# P09_USER_LED_FAN_WD_RTC.net
KiCad netlist of a schematic drawn in Altium Designer
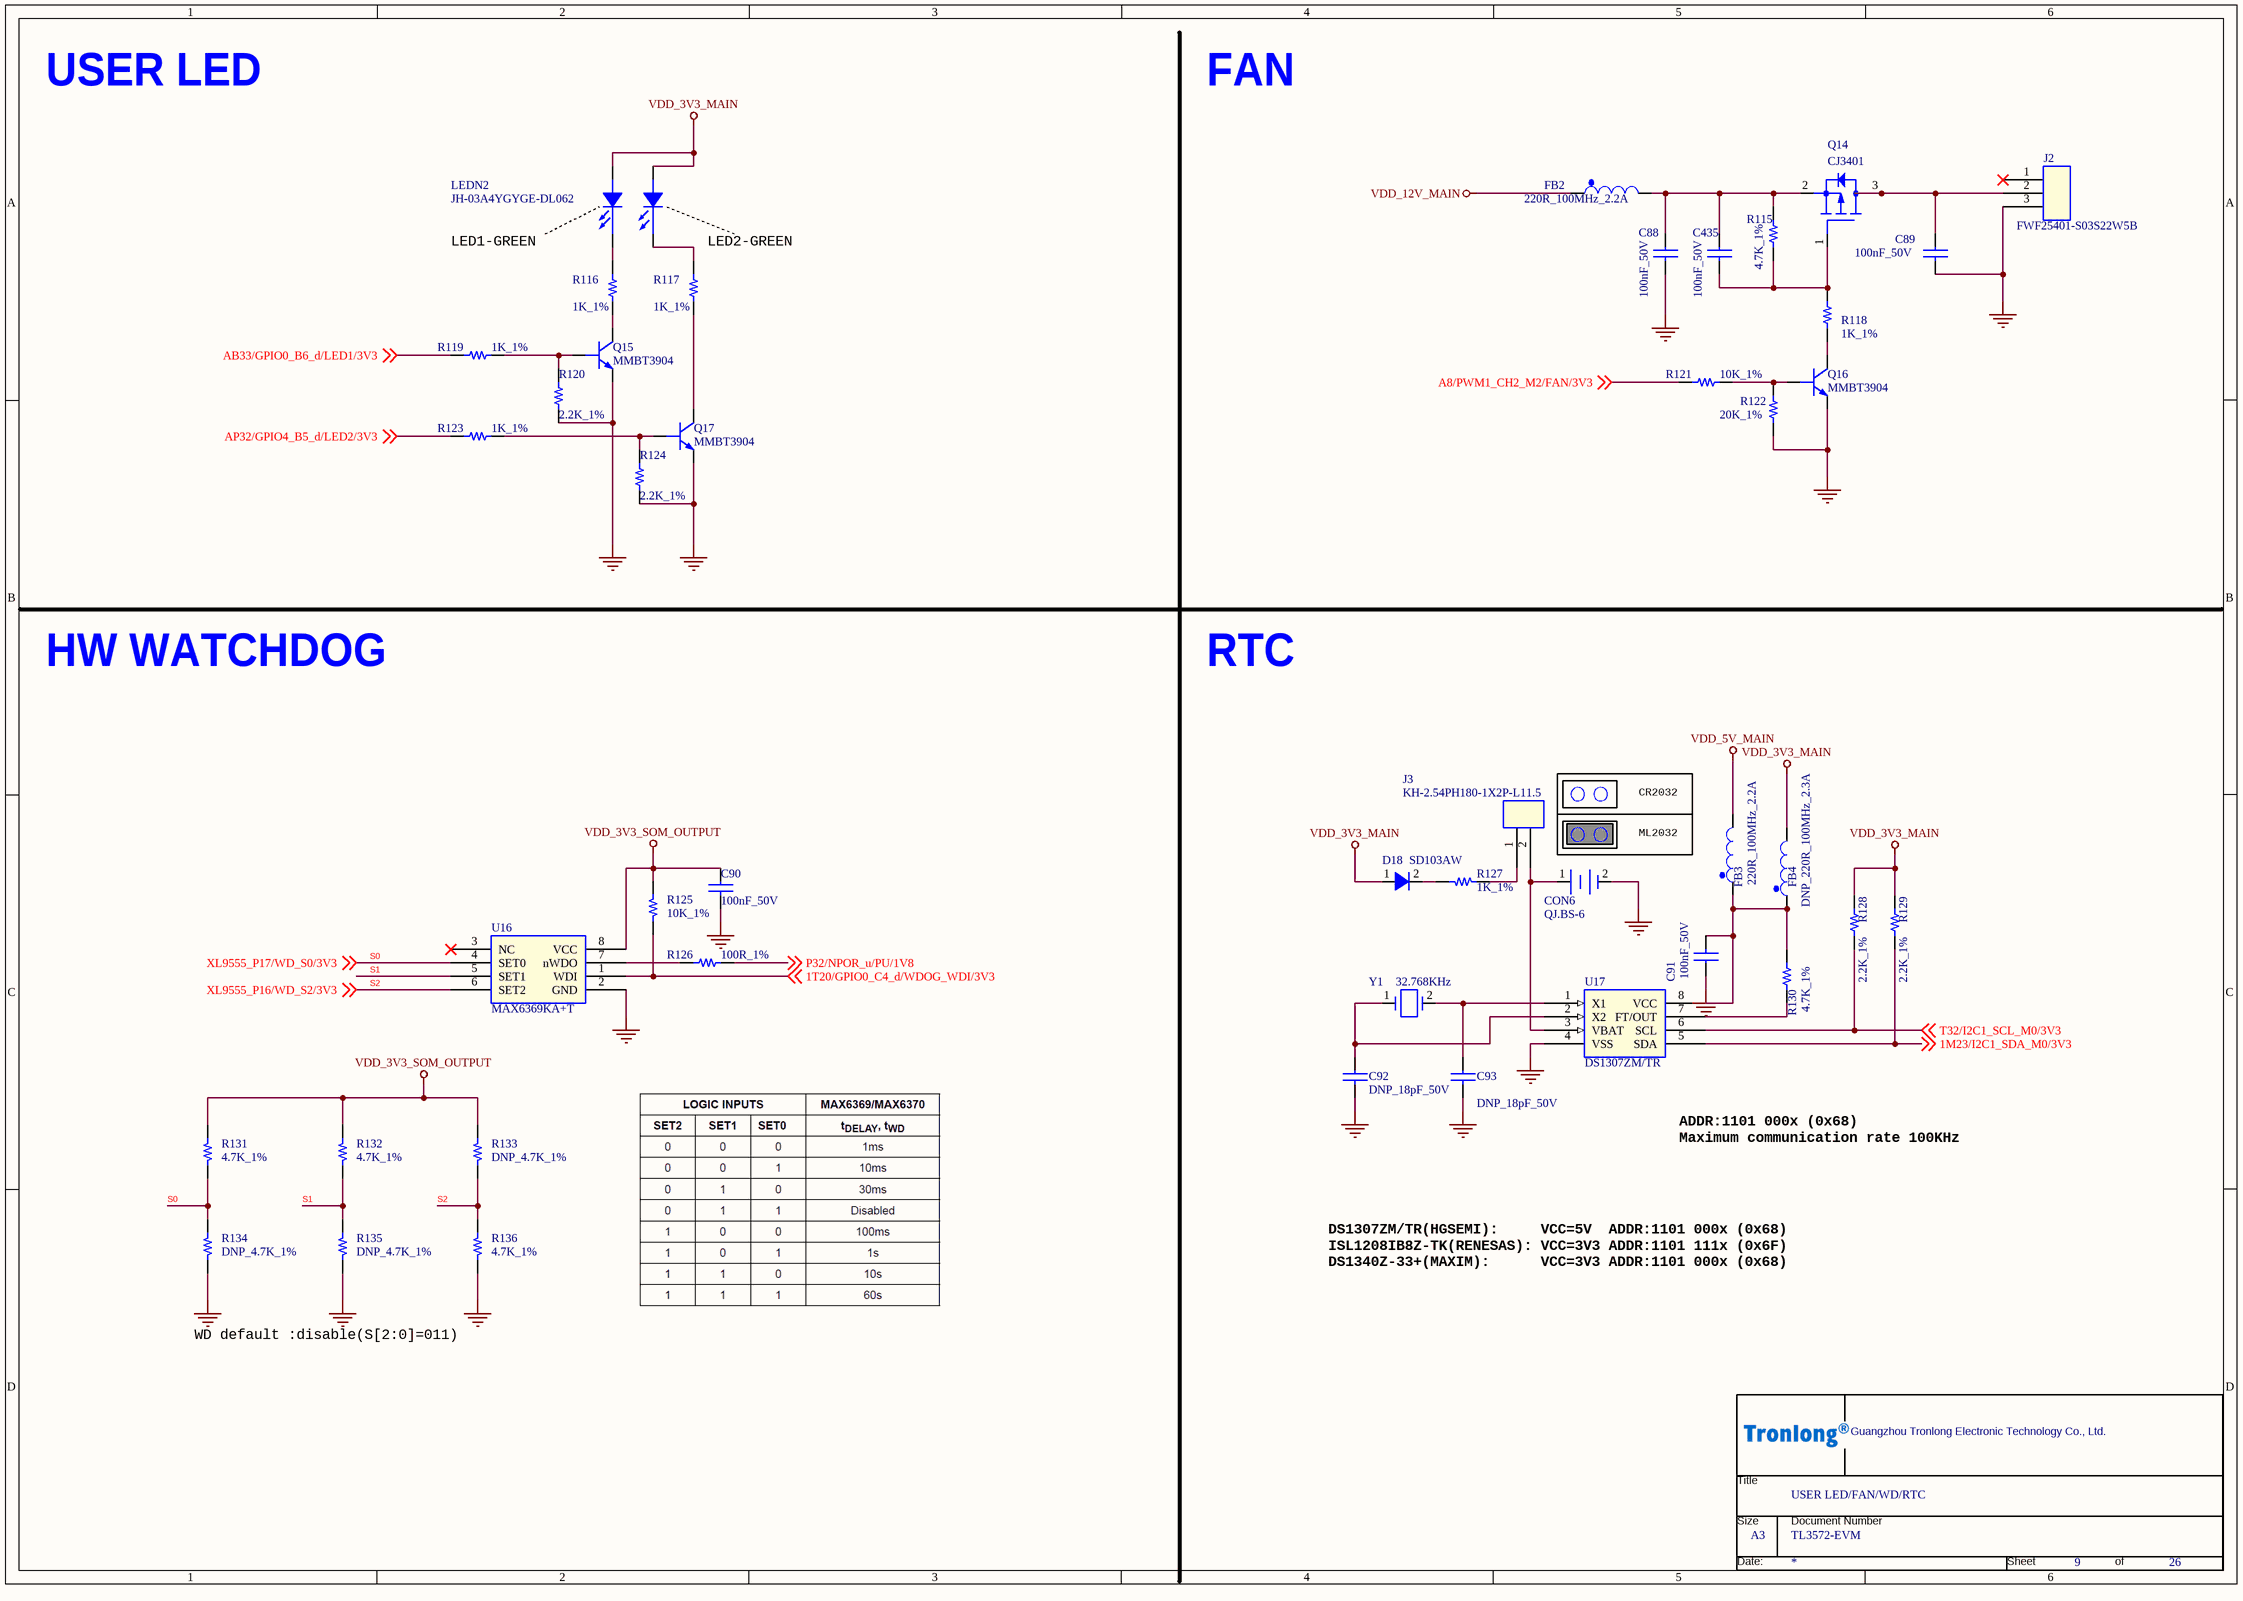
[diagram p0: P09_USER LED_FAN_WD_RTC.SchDoc]

(export (version "E")
  (design (tool "Eeschema 10.0.6"))
  (components
    (comp (ref "*")
      (value "TL_NEW")
      (fields
        (field (name "PAGE COUNT") "26")
        (field (name "PAGE NUMBER") "9")
        (field (name "PAGE SIZE") "A3")
        (field (name "ORGNAME") "Guangzhou Tronlong Electronic Technology Co., Ltd.")
        (field (name "TITLE") "USER LED/FAN/WD/RTC")
        (field (name "DOC") "TL3572-EVM")
      )
      (libsource (lib "*") (part "TL_NEW"))
    )
    (comp (ref "C88")
      (value "100nF_50V")
      (footprint "C0402")
      (description "贴片陶瓷电容,100nF,10%,50V,X7R")
      (fields
        (field (name "MANUFACTURER PARTNUMBER") "0402B104K500NT")
        (field (name "MANUFACTURER") "广东风华高新科技股份有限公司（FH）")
      )
      (libsource (lib "*") (part "CAP NP_Dup2"))
    )
    (comp (ref "C89")
      (value "100nF_50V")
      (footprint "C0402")
      (description "贴片陶瓷电容,100nF,10%,50V,X7R")
      (fields
        (field (name "MANUFACTURER PARTNUMBER") "0402B104K500NT")
        (field (name "MANUFACTURER") "广东风华高新科技股份有限公司（FH）")
      )
      (libsource (lib "*") (part "CAP NP_Dup2"))
    )
    (comp (ref "C90")
      (value "100nF_50V")
      (footprint "C0402")
      (description "贴片陶瓷电容,100nF,10%,50V,X7R")
      (fields
        (field (name "MANUFACTURER PARTNUMBER") "0402B104K500NT")
        (field (name "MANUFACTURER") "广东风华高新科技股份有限公司（FH）")
      )
      (libsource (lib "*") (part "CAP NP_Dup2"))
    )
    (comp (ref "C91")
      (value "100nF_50V")
      (footprint "C0402")
      (description "贴片陶瓷电容,100nF,10%,50V,X7R")
      (fields
        (field (name "MANUFACTURER PARTNUMBER") "0402B104K500NT")
        (field (name "MANUFACTURER") "广东风华高新科技股份有限公司（FH）")
      )
      (libsource (lib "*") (part "CAP NP_Dup2"))
    )
    (comp (ref "C92")
      (value "DNP_18pF_50V")
      (footprint "C0603")
      (description "贴片陶瓷电容,18pF,5%,50V,COG")
      (fields
        (field (name "MANUFACTURER PARTNUMBER") "0603CG180J500NT")
        (field (name "MANUFACTURER") "广东风华高新科技股份有限公司（FH）")
      )
      (libsource (lib "*") (part "CAP NP_Dup2"))
    )
    (comp (ref "C93")
      (value "DNP_18pF_50V")
      (footprint "C0603")
      (description "贴片陶瓷电容,18pF,5%,50V,COG")
      (fields
        (field (name "MANUFACTURER PARTNUMBER") "0603CG180J500NT")
        (field (name "MANUFACTURER") "广东风华高新科技股份有限公司（FH）")
      )
      (libsource (lib "*") (part "CAP NP_Dup2"))
    )
    (comp (ref "C435")
      (value "100nF_50V")
      (footprint "C0402")
      (description "贴片陶瓷电容,100nF,10%,50V,X7R")
      (fields
        (field (name "MANUFACTURER PARTNUMBER") "0402B104K500NT")
        (field (name "MANUFACTURER") "广东风华高新科技股份有限公司（FH）")
      )
      (libsource (lib "*") (part "CAP NP_Dup2"))
    )
    (comp (ref "CON6")
      (value "QJ.BS-6")
      (footprint "CON_BATTERY_CR2032")
      (description "贴片纽扣电池座,CR2032,2P,180度")
      (fields (field (name "MANUFACTURER") "深圳市琦捷电子有限公司（QIJEY）"))
      (libsource (lib "*") (part "BATTERY"))
    )
    (comp (ref "D18")
      (value "SD103AW")
      (footprint "SOD-123_NEW")
      (description "肖特基二极管,VR=40V,IF=350mA,VF=0.37V@20mA,trr=10ns")
      (fields (field (name "TIINTPARTNUMBER") "1E0013") (field (name "MFR") "On Semiconductor"))
      (libsource (lib "*") (part "Diode200mA250V_1"))
    )
    (comp (ref "FB2")
      (value "220R_100MHz_2.2A")
      (footprint "L0603")
      (description "磁珠,50mΩ,2.2A,220R@100MHz")
      (fields
        (field (name "MANUFACTURER PARTNUMBER") "UPZ1608U221-2R2TF")
        (field (name "MANUFACTURER") "深圳顺络电子股份有限公司（Sunlord）")
      )
      (libsource (lib "*") (part "FB_0"))
    )
    (comp (ref "FB3")
      (value "220R_100MHz_2.2A")
      (footprint "L0603")
      (description "磁珠,50mΩ,2.2A,220R@100MHz")
      (fields
        (field (name "MANUFACTURER PARTNUMBER") "UPZ1608U221-2R2TF")
        (field (name "MANUFACTURER") "深圳顺络电子股份有限公司（Sunlord）")
      )
      (libsource (lib "*") (part "FERRITE BEAD_Dup1"))
    )
    (comp (ref "FB4")
      (value "DNP_220R_100MHz_2.3A")
      (footprint "L0603")
      (description "磁珠,50mΩ,2.3A,220R@100MHz")
      (fields
        (field (name "MANUFACTURER") "深圳顺络电子股份有限公司（Sunlord）")
        (field (name "MANUFACTURER PARTNUMBER") "UPZ1608U221-2R3TF")
      )
      (libsource (lib "*") (part "FERRITE BEAD_Dup1"))
    )
    (comp (ref "J2")
      (value "FWF25401-S03S22W5B")
      (footprint "mol22-23-2031")
      (description "插件针座连接器,3P,间距2.54mm,180度,白色")
      (fields (field (name "MANUFACTURER") "深圳特思嘉工业电子有限公司（TXGA）"))
      (libsource (lib "*") (part "CON3"))
    )
    (comp (ref "J3")
      (value "KH-2.54PH180-1X2P-L11.5")
      (footprint "header_1x2p_2d54_male")
      (description "插件单排排针,1x2P,2.54mm,180度")
      (fields (field (name "MANUFACTURER") "深圳市金航标电子有限公司(kinghelm)"))
      (libsource (lib "*") (part "CON2_0"))
    )
    (comp (ref "LEDN2")
      (value "JH-03A4YGYGE-DL062")
      (footprint "led-th_4p-l12d8-w4d6")
      (description "直插式发光二极管,绿色,带灯座")
      (fields
        (field (name "MANUFACTURER") "深圳市巨弘光电有限公司（JUHLIGHT）")
        (field (name "MANUFACTURER PARTNUMBER") "JH-03B2YG1E-DL")
      )
      (libsource (lib "*") (part "LED_4"))
    )
    (comp (ref "Q14")
      (value "CJ3401")
      (footprint "SOT23-3")
      (description "MOSFET,P沟道,VDSS=-30V,VGSS=±12V,ID=-4.2A,PD=0.35W,VGS(th)=-1.3V")
      (fields (field (name "MANUFACTURER") "江苏长晶科技股份有限公司（JSCJ）"))
      (libsource (lib "*") (part "MOSFET P SOT_Dup1"))
    )
    (comp (ref "Q15")
      (value "MMBT3904")
      (footprint "SOT23-3_DBZ3")
      (description "BJT,NPN,Vceo=40V,Ic=200mA,fT=300MHz,PD=200mW")
      (fields (field (name "MANUFACTURER") "江苏长晶科技股份有限公司（JSCJ）"))
      (libsource (lib "*") (part "MMBT3904/SOT"))
    )
    (comp (ref "Q16")
      (value "MMBT3904")
      (footprint "SOT23-3_DBZ3")
      (description "BJT,NPN,Vceo=40V,Ic=200mA,fT=300MHz,PD=200mW")
      (fields (field (name "MANUFACTURER") "江苏长晶科技股份有限公司（JSCJ）"))
      (libsource (lib "*") (part "MMBT3904/SOT"))
    )
    (comp (ref "Q17")
      (value "MMBT3904")
      (footprint "SOT23-3_DBZ3")
      (description "BJT,NPN,Vceo=40V,Ic=200mA,fT=300MHz,PD=200mW")
      (fields (field (name "MANUFACTURER") "江苏长晶科技股份有限公司（JSCJ）"))
      (libsource (lib "*") (part "MMBT3904/SOT"))
    )
    (comp (ref "R115")
      (value "4.7K_1%")
      (footprint "R0402")
      (description "贴片电阻,4.7K,±1%,1/16W")
      (fields
        (field (name "MANUFACTURER") "广东风华高新科技股份有限公司（FH）")
        (field (name "MISTRAL PART NO") "110009031036-R")
      )
      (libsource (lib "*") (part "Resistor_Dup3"))
    )
    (comp (ref "R116")
      (value "1K_1%")
      (footprint "R0603")
      (description "贴片电阻,1K,±1%,1/10W")
      (fields
        (field (name "MANUFACTURER PARTNUMBER") "RS-03K1001FT")
        (field (name "MANUFACTURER") "广东风华高新科技股份有限公司（FH）")
      )
      (libsource (lib "*") (part "Resistor_Dup4"))
    )
    (comp (ref "R117")
      (value "1K_1%")
      (footprint "R0603")
      (description "贴片电阻,1K,±1%,1/10W")
      (fields
        (field (name "MANUFACTURER") "广东风华高新科技股份有限公司（FH）")
        (field (name "MANUFACTURER PARTNUMBER") "RS-03K1001FT")
      )
      (libsource (lib "*") (part "Resistor_Dup4"))
    )
    (comp (ref "R118")
      (value "1K_1%")
      (footprint "R0603")
      (description "贴片电阻,1K,±1%,1/10W")
      (fields
        (field (name "MANUFACTURER") "广东风华高新科技股份有限公司（FH）")
        (field (name "MISTRAL PART NO") "110009031036-R")
      )
      (libsource (lib "*") (part "Resistor_Dup3"))
    )
    (comp (ref "R119")
      (value "1K_1%")
      (footprint "R0402")
      (description "贴片电阻,1K,±1%,1/16W")
      (fields
        (field (name "MANUFACTURER PARTNUMBER") "RC-02K1001FT")
        (field (name "MANUFACTURER") "广东风华高新科技股份有限公司（FH）")
      )
      (libsource (lib "*") (part "Resistor_Dup4"))
    )
    (comp (ref "R120")
      (value "2.2K_1%")
      (footprint "R0603")
      (description "贴片电阻,2.2K,±1%,1/10W")
      (fields
        (field (name "MANUFACTURER") "广东风华高新科技股份有限公司（FH）")
        (field (name "MANUFACTURER PARTNUMBER") "RS-03K2201FT")
      )
      (libsource (lib "*") (part "Resistor_Dup4"))
    )
    (comp (ref "R121")
      (value "10K_1%")
      (footprint "R0402")
      (description "贴片电阻,10K,±1%,1/16W")
      (fields
        (field (name "MANUFACTURER PARTNUMBER") "RC-02K1002FT")
        (field (name "MISTRAL PART NO") "110009031036-R")
      )
      (libsource (lib "*") (part "Resistor_Dup3"))
    )
    (comp (ref "R122")
      (value "20K_1%")
      (footprint "R0603")
      (description "贴片电阻,20K,±1%,1/10W")
      (fields
        (field (name "MANUFACTURER") "广东风华高新科技股份有限公司（FH）")
        (field (name "MANUFACTURER PARTNUMBER") "RS-03K2002FT")
      )
      (libsource (lib "*") (part "Resistor_Dup3"))
    )
    (comp (ref "R123")
      (value "1K_1%")
      (footprint "R0603")
      (description "贴片电阻,1K,±1%,1/10W")
      (fields
        (field (name "MANUFACTURER PARTNUMBER") "RS-03K1001FT")
        (field (name "MANUFACTURER") "广东风华高新科技股份有限公司（FH）")
      )
      (libsource (lib "*") (part "Resistor_Dup4"))
    )
    (comp (ref "R124")
      (value "2.2K_1%")
      (footprint "R0603")
      (description "贴片电阻,2.2K,±1%,1/10W")
      (fields
        (field (name "MANUFACTURER PARTNUMBER") "RS-03K2201FT")
        (field (name "MANUFACTURER") "广东风华高新科技股份有限公司（FH）")
      )
      (libsource (lib "*") (part "Resistor_Dup4"))
    )
    (comp (ref "R125")
      (value "10K_1%")
      (footprint "R0402")
      (description "贴片电阻,10K,±1%,1/16W")
      (fields
        (field (name "MANUFACTURER") "广东风华高新科技股份有限公司（FH）")
        (field (name "MANUFACTURER PARTNUMBER") "RC-02K1002FT")
      )
      (libsource (lib "*") (part "Resistor_Dup4"))
    )
    (comp (ref "R126")
      (value "100R_1%")
      (footprint "R0402")
      (description "贴片电阻,100R,±1%,1/16W")
      (fields
        (field (name "MANUFACTURER PARTNUMBER") "RC-02K1000FT")
        (field (name "MANUFACTURER") "广东风华高新科技股份有限公司（FH）")
      )
      (libsource (lib "*") (part "Resistor_Dup4"))
    )
    (comp (ref "R127")
      (value "1K_1%")
      (footprint "R0603")
      (description "贴片电阻,1K,±1%,1/10W")
      (fields
        (field (name "MANUFACTURER PARTNUMBER") "RS-03K1001FT")
        (field (name "MANUFACTURER") "广东风华高新科技股份有限公司（FH）")
      )
      (libsource (lib "*") (part "Resistor_Dup3"))
    )
    (comp (ref "R128")
      (value "2.2K_1%")
      (footprint "R0603")
      (description "贴片电阻,2.2K,±1%,1/10W")
      (fields
        (field (name "MANUFACTURER") "广东风华高新科技股份有限公司（FH）")
        (field (name "MANUFACTURER PARTNUMBER") "RS-03K2201FT")
      )
      (libsource (lib "*") (part "Resistor_Dup4"))
    )
    (comp (ref "R129")
      (value "2.2K_1%")
      (footprint "R0603")
      (description "贴片电阻,2.2K,±1%,1/10W")
      (fields
        (field (name "MANUFACTURER") "广东风华高新科技股份有限公司（FH）")
        (field (name "MANUFACTURER PARTNUMBER") "RS-03K2201FT")
      )
      (libsource (lib "*") (part "Resistor_Dup4"))
    )
    (comp (ref "R130")
      (value "4.7K_1%")
      (footprint "R0402")
      (description "贴片电阻,4.7K,±1%,1/16W")
      (fields
        (field (name "MANUFACTURER PARTNUMBER") "RC-02K4701FT")
        (field (name "MANUFACTURER") "广东风华高新科技股份有限公司（FH）")
      )
      (libsource (lib "*") (part "Resistor_Dup3"))
    )
    (comp (ref "R131")
      (value "4.7K_1%")
      (footprint "R0402")
      (description "贴片电阻,4.7K,±1%,1/16W")
      (fields
        (field (name "MANUFACTURER PARTNUMBER") "RC-02K4701FT")
        (field (name "MANUFACTURER") "广东风华高新科技股份有限公司（FH）")
      )
      (libsource (lib "*") (part "Resistor_Dup3"))
    )
    (comp (ref "R132")
      (value "4.7K_1%")
      (footprint "R0402")
      (description "贴片电阻,4.7K,±1%,1/16W")
      (fields
        (field (name "MANUFACTURER") "广东风华高新科技股份有限公司（FH）")
        (field (name "MANUFACTURER PARTNUMBER") "RC-02K4701FT")
      )
      (libsource (lib "*") (part "Resistor_Dup3"))
    )
    (comp (ref "R133")
      (value "DNP_4.7K_1%")
      (footprint "R0402")
      (description "RC0402FR-074K7L,0402WGF4701TCE")
      (fields
        (field (name "MANUFACTURER") "广州创龙")
        (field (name "MANUFACTURER PARTNUMBER") "4.7K,±1%,R0402,≥1/16W")
      )
      (libsource (lib "*") (part "Resistor_Dup3"))
    )
    (comp (ref "R134")
      (value "DNP_4.7K_1%")
      (footprint "R0402")
      (description "RC0402FR-074K7L,0402WGF4701TCE")
      (fields
        (field (name "MANUFACTURER") "广州创龙")
        (field (name "MANUFACTURER PARTNUMBER") "4.7K,±1%,R0402,≥1/16W")
      )
      (libsource (lib "*") (part "Resistor_Dup3"))
    )
    (comp (ref "R135")
      (value "DNP_4.7K_1%")
      (footprint "R0402")
      (description "RC0402FR-074K7L,0402WGF4701TCE")
      (fields
        (field (name "MANUFACTURER PARTNUMBER") "4.7K,±1%,R0402,≥1/16W")
        (field (name "MANUFACTURER") "广州创龙")
      )
      (libsource (lib "*") (part "Resistor_Dup3"))
    )
    (comp (ref "R136")
      (value "4.7K_1%")
      (footprint "R0402")
      (description "贴片电阻,4.7K,±1%,1/16W")
      (fields
        (field (name "MANUFACTURER") "广东风华高新科技股份有限公司（FH）")
        (field (name "MANUFACTURER PARTNUMBER") "RC-02K4701FT")
      )
      (libsource (lib "*") (part "Resistor_Dup3"))
    )
    (comp (ref "U16")
      (value "MAX6369KA+T")
      (footprint "sot23_8")
      (description "低电平有效开漏输出,2.5V-5.5V,-40~125℃")
      (fields (field (name "MANUFACTURER") "Maxim Integrated（美国美信）"))
      (libsource (lib "*") (part "MAX637x"))
    )
    (comp (ref "U17")
      (value "DS1307ZM/TR")
      (footprint "SOIC8_D8")
      (description "实时时钟,VCC=4.5~5.5V,I2C")
      (fields (field (name "MANUFACTURER") "广东华冠半导体有限公司(HGSEMI)"))
      (libsource (lib "*") (part "IC_MCP79410_0"))
    )
    (comp (ref "Y1")
      (value "32.768KHz")
      (footprint "SMD_2012")
      (description "两脚无源晶振,32.768KHz,±20ppm,12.5pF,80KΩ,±20ppm")
      (fields (field (name "MFR") "Epson") (field (name "TIINTPARTNUMBER") "1Y0029"))
      (libsource (lib "*") (part "CRYS_32_768KHz_SMD"))
    )
  )
  (nets
    (net (code "1") (name "/S1") (class "Default")
      (node (ref "R132") (pin "2") (pinfunction "2_2") (pintype "passive"))
      (node (ref "R135") (pin "1") (pinfunction "1_1") (pintype "passive"))
      (node (ref "U16") (pin "5") (pinfunction "SET1_5") (pintype "passive"))
    )
    (net (code "2") (name "1M23{slash}I2C1_SDA_M0{slash}3V3") (class "Default")
      (node (ref "R129") (pin "2") (pinfunction "2_2") (pintype "passive"))
      (node (ref "U17") (pin "5") (pinfunction "SDA_5") (pintype "passive"))
    )
    (net (code "3") (name "1T20{slash}GPIO0_C4_d{slash}WDOG_WDI{slash}3V3") (class "Default")
      (node (ref "R125") (pin "2") (pinfunction "2_2") (pintype "passive"))
      (node (ref "U16") (pin "1") (pinfunction "WDI_1") (pintype "passive"))
    )
    (net (code "4") (name "A8{slash}PWM1_CH2_M2{slash}FAN{slash}3V3") (class "Default")
      (node (ref "R121") (pin "1") (pinfunction "1_1") (pintype "passive"))
    )
    (net (code "5") (name "AB33{slash}GPIO0_B6_d{slash}LED1{slash}3V3") (class "Default")
      (node (ref "R119") (pin "2") (pinfunction "2_2") (pintype "passive"))
    )
    (net (code "6") (name "AP32{slash}GPIO4_B5_d{slash}LED2{slash}3V3") (class "Default")
      (node (ref "R123") (pin "2") (pinfunction "2_2") (pintype "passive"))
    )
    (net (code "7") (name "GND") (class "Default")
      (node (ref "C88") (pin "2") (pinfunction "2_2") (pintype "passive"))
      (node (ref "C89") (pin "2") (pinfunction "2_2") (pintype "passive"))
      (node (ref "C90") (pin "2") (pinfunction "2_2") (pintype "passive"))
      (node (ref "C91") (pin "1") (pinfunction "1_1") (pintype "passive"))
      (node (ref "C92") (pin "2") (pinfunction "2_2") (pintype "passive"))
      (node (ref "C93") (pin "2") (pinfunction "2_2") (pintype "passive"))
      (node (ref "CON6") (pin "2") (pinfunction "-_2") (pintype "passive"))
      (node (ref "J2") (pin "3") (pinfunction "3_3") (pintype "passive"))
      (node (ref "Q15") (pin "2") (pinfunction "E_2") (pintype "passive"))
      (node (ref "Q16") (pin "2") (pinfunction "E_2") (pintype "passive"))
      (node (ref "Q17") (pin "2") (pinfunction "E_2") (pintype "passive"))
      (node (ref "R120") (pin "1") (pinfunction "1_1") (pintype "passive"))
      (node (ref "R122") (pin "2") (pinfunction "2_2") (pintype "passive"))
      (node (ref "R124") (pin "1") (pinfunction "1_1") (pintype "passive"))
      (node (ref "R134") (pin "2") (pinfunction "2_2") (pintype "passive"))
      (node (ref "R135") (pin "2") (pinfunction "2_2") (pintype "passive"))
      (node (ref "R136") (pin "2") (pinfunction "2_2") (pintype "passive"))
      (node (ref "U16") (pin "2") (pinfunction "GND_2") (pintype "passive"))
      (node (ref "U17") (pin "4") (pinfunction "VSS_4") (pintype "power_in"))
    )
    (net (code "8") (name "Net-(CON6-+)") (class "Default")
      (node (ref "CON6") (pin "1") (pinfunction "+_1") (pintype "passive"))
      (node (ref "J3") (pin "2") (pinfunction "2_2") (pintype "passive"))
      (node (ref "U17") (pin "3") (pinfunction "VBAT_3") (pintype "input"))
    )
    (net (code "9") (name "Net-(D18-Cathode)") (class "Default")
      (node (ref "D18") (pin "2") (pinfunction "Cathode_2") (pintype "passive"))
      (node (ref "R127") (pin "2") (pinfunction "2_2") (pintype "passive"))
    )
    (net (code "10") (name "Net-(J3-Pad1)") (class "Default")
      (node (ref "J3") (pin "1") (pinfunction "1_1") (pintype "passive"))
      (node (ref "R127") (pin "1") (pinfunction "1_1") (pintype "passive"))
    )
    (net (code "11") (name "Net-(LEDN2-CATHODE1)") (class "Default")
      (node (ref "LEDN2") (pin "1") (pinfunction "CATHODE1_1") (pintype "passive"))
      (node (ref "R116") (pin "2") (pinfunction "2_2") (pintype "passive"))
    )
    (net (code "12") (name "Net-(LEDN2-CATHODE2)") (class "Default")
      (node (ref "LEDN2") (pin "4") (pinfunction "CATHODE2_4") (pintype "passive"))
      (node (ref "R117") (pin "2") (pinfunction "2_2") (pintype "passive"))
    )
    (net (code "13") (name "Net-(Q14-DRAIN)") (class "Default")
      (node (ref "C89") (pin "1") (pinfunction "1_1") (pintype "passive"))
      (node (ref "J2") (pin "2") (pinfunction "2_2") (pintype "passive"))
      (node (ref "Q14") (pin "3") (pinfunction "DRAIN_3") (pintype "passive"))
    )
    (net (code "14") (name "Net-(Q14-GATE)") (class "Default")
      (node (ref "C435") (pin "2") (pinfunction "2_2") (pintype "passive"))
      (node (ref "Q14") (pin "1") (pinfunction "GATE_1") (pintype "passive"))
      (node (ref "R115") (pin "2") (pinfunction "2_2") (pintype "passive"))
      (node (ref "R118") (pin "1") (pinfunction "1_1") (pintype "passive"))
    )
    (net (code "15") (name "Net-(Q14-SOURCE)") (class "Default")
      (node (ref "C435") (pin "1") (pinfunction "1_1") (pintype "passive"))
      (node (ref "C88") (pin "1") (pinfunction "1_1") (pintype "passive"))
      (node (ref "FB2") (pin "2") (pinfunction "2_2") (pintype "passive"))
      (node (ref "Q14") (pin "2") (pinfunction "SOURCE_2") (pintype "passive"))
      (node (ref "R115") (pin "1") (pinfunction "1_1") (pintype "passive"))
    )
    (net (code "16") (name "Net-(Q15-B)") (class "Default")
      (node (ref "Q15") (pin "1") (pinfunction "B_1") (pintype "passive"))
      (node (ref "R119") (pin "1") (pinfunction "1_1") (pintype "passive"))
      (node (ref "R120") (pin "2") (pinfunction "2_2") (pintype "passive"))
    )
    (net (code "17") (name "Net-(Q15-C)") (class "Default")
      (node (ref "Q15") (pin "3") (pinfunction "C_3") (pintype "passive"))
      (node (ref "R116") (pin "1") (pinfunction "1_1") (pintype "passive"))
    )
    (net (code "18") (name "Net-(Q16-B)") (class "Default")
      (node (ref "Q16") (pin "1") (pinfunction "B_1") (pintype "passive"))
      (node (ref "R121") (pin "2") (pinfunction "2_2") (pintype "passive"))
      (node (ref "R122") (pin "1") (pinfunction "1_1") (pintype "passive"))
    )
    (net (code "19") (name "Net-(Q16-C)") (class "Default")
      (node (ref "Q16") (pin "3") (pinfunction "C_3") (pintype "passive"))
      (node (ref "R118") (pin "2") (pinfunction "2_2") (pintype "passive"))
    )
    (net (code "20") (name "Net-(Q17-B)") (class "Default")
      (node (ref "Q17") (pin "1") (pinfunction "B_1") (pintype "passive"))
      (node (ref "R123") (pin "1") (pinfunction "1_1") (pintype "passive"))
      (node (ref "R124") (pin "2") (pinfunction "2_2") (pintype "passive"))
    )
    (net (code "21") (name "Net-(Q17-C)") (class "Default")
      (node (ref "Q17") (pin "3") (pinfunction "C_3") (pintype "passive"))
      (node (ref "R117") (pin "1") (pinfunction "1_1") (pintype "passive"))
    )
    (net (code "22") (name "Net-(U16-nWDO)") (class "Default")
      (node (ref "R126") (pin "1") (pinfunction "1_1") (pintype "passive"))
      (node (ref "U16") (pin "7") (pinfunction "nWDO_7") (pintype "passive"))
    )
    (net (code "23") (name "Net-(U17-FT{slash}OUT)") (class "Default")
      (node (ref "R130") (pin "2") (pinfunction "2_2") (pintype "passive"))
      (node (ref "U17") (pin "7") (pinfunction "FT/OUT_7") (pintype "passive"))
    )
    (net (code "24") (name "Net-(U17-VCC)") (class "Default")
      (node (ref "C91") (pin "2") (pinfunction "2_2") (pintype "passive"))
      (node (ref "FB3") (pin "1") (pinfunction "1_1") (pintype "passive"))
      (node (ref "FB4") (pin "1") (pinfunction "1_1") (pintype "passive"))
      (node (ref "R130") (pin "1") (pinfunction "1_1") (pintype "passive"))
      (node (ref "U17") (pin "8") (pinfunction "VCC_8") (pintype "power_in"))
    )
    (net (code "25") (name "Net-(U17-X1)") (class "Default")
      (node (ref "C93") (pin "1") (pinfunction "1_1") (pintype "passive"))
      (node (ref "U17") (pin "1") (pinfunction "X1_1") (pintype "input"))
      (node (ref "Y1") (pin "2") (pinfunction "2_2") (pintype "passive"))
    )
    (net (code "26") (name "Net-(U17-X2)") (class "Default")
      (node (ref "C92") (pin "1") (pinfunction "1_1") (pintype "passive"))
      (node (ref "U17") (pin "2") (pinfunction "X2_2") (pintype "input"))
      (node (ref "Y1") (pin "1") (pinfunction "1_1") (pintype "passive"))
    )
    (net (code "27") (name "P32{slash}NPOR_u{slash}PU{slash}1V8") (class "Default")
      (node (ref "R126") (pin "2") (pinfunction "2_2") (pintype "passive"))
    )
    (net (code "28") (name "T32{slash}I2C1_SCL_M0{slash}3V3") (class "Default")
      (node (ref "R128") (pin "2") (pinfunction "2_2") (pintype "passive"))
      (node (ref "U17") (pin "6") (pinfunction "SCL_6") (pintype "passive"))
    )
    (net (code "29") (name "VDD_3V3_MAIN") (class "Default")
      (node (ref "D18") (pin "1") (pinfunction "Anode_1") (pintype "passive"))
      (node (ref "FB4") (pin "2") (pinfunction "2_2") (pintype "passive"))
      (node (ref "LEDN2") (pin "2") (pinfunction "ANODE1_2") (pintype "passive"))
      (node (ref "LEDN2") (pin "3") (pinfunction "ANODE2_3") (pintype "passive"))
      (node (ref "R128") (pin "1") (pinfunction "1_1") (pintype "passive"))
      (node (ref "R129") (pin "1") (pinfunction "1_1") (pintype "passive"))
    )
    (net (code "30") (name "VDD_3V3_SOM_OUTPUT") (class "Default")
      (node (ref "C90") (pin "1") (pinfunction "1_1") (pintype "passive"))
      (node (ref "R125") (pin "1") (pinfunction "1_1") (pintype "passive"))
      (node (ref "R131") (pin "1") (pinfunction "1_1") (pintype "passive"))
      (node (ref "R132") (pin "1") (pinfunction "1_1") (pintype "passive"))
      (node (ref "R133") (pin "1") (pinfunction "1_1") (pintype "passive"))
      (node (ref "U16") (pin "8") (pinfunction "VCC_8") (pintype "passive"))
    )
    (net (code "31") (name "VDD_5V_MAIN") (class "Default")
      (node (ref "FB3") (pin "2") (pinfunction "2_2") (pintype "passive"))
    )
    (net (code "32") (name "VDD_12V_MAIN") (class "Default")
      (node (ref "FB2") (pin "1") (pinfunction "1_1") (pintype "passive"))
    )
    (net (code "33") (name "XL9555_P16{slash}WD_S2{slash}3V3") (class "Default")
      (node (ref "R133") (pin "2") (pinfunction "2_2") (pintype "passive"))
      (node (ref "R136") (pin "1") (pinfunction "1_1") (pintype "passive"))
      (node (ref "U16") (pin "6") (pinfunction "SET2_6") (pintype "passive"))
    )
    (net (code "34") (name "XL9555_P17{slash}WD_S0{slash}3V3") (class "Default")
      (node (ref "R131") (pin "2") (pinfunction "2_2") (pintype "passive"))
      (node (ref "R134") (pin "1") (pinfunction "1_1") (pintype "passive"))
      (node (ref "U16") (pin "4") (pinfunction "SET0_4") (pintype "passive"))
    )
    (net (code "35") (name "unconnected-(J2-Pad1)") (class "Default")
      (node (ref "J2") (pin "1") (pinfunction "1_1") (pintype "passive+no_connect"))
    )
    (net (code "36") (name "unconnected-(U16-NC-Pad3)") (class "Default")
      (node (ref "U16") (pin "3") (pinfunction "NC_3") (pintype "passive+no_connect"))
    )
  )
)
